# TapDriver-ESP32.net
KiCad netlist of a schematic drawn in Altium Designer
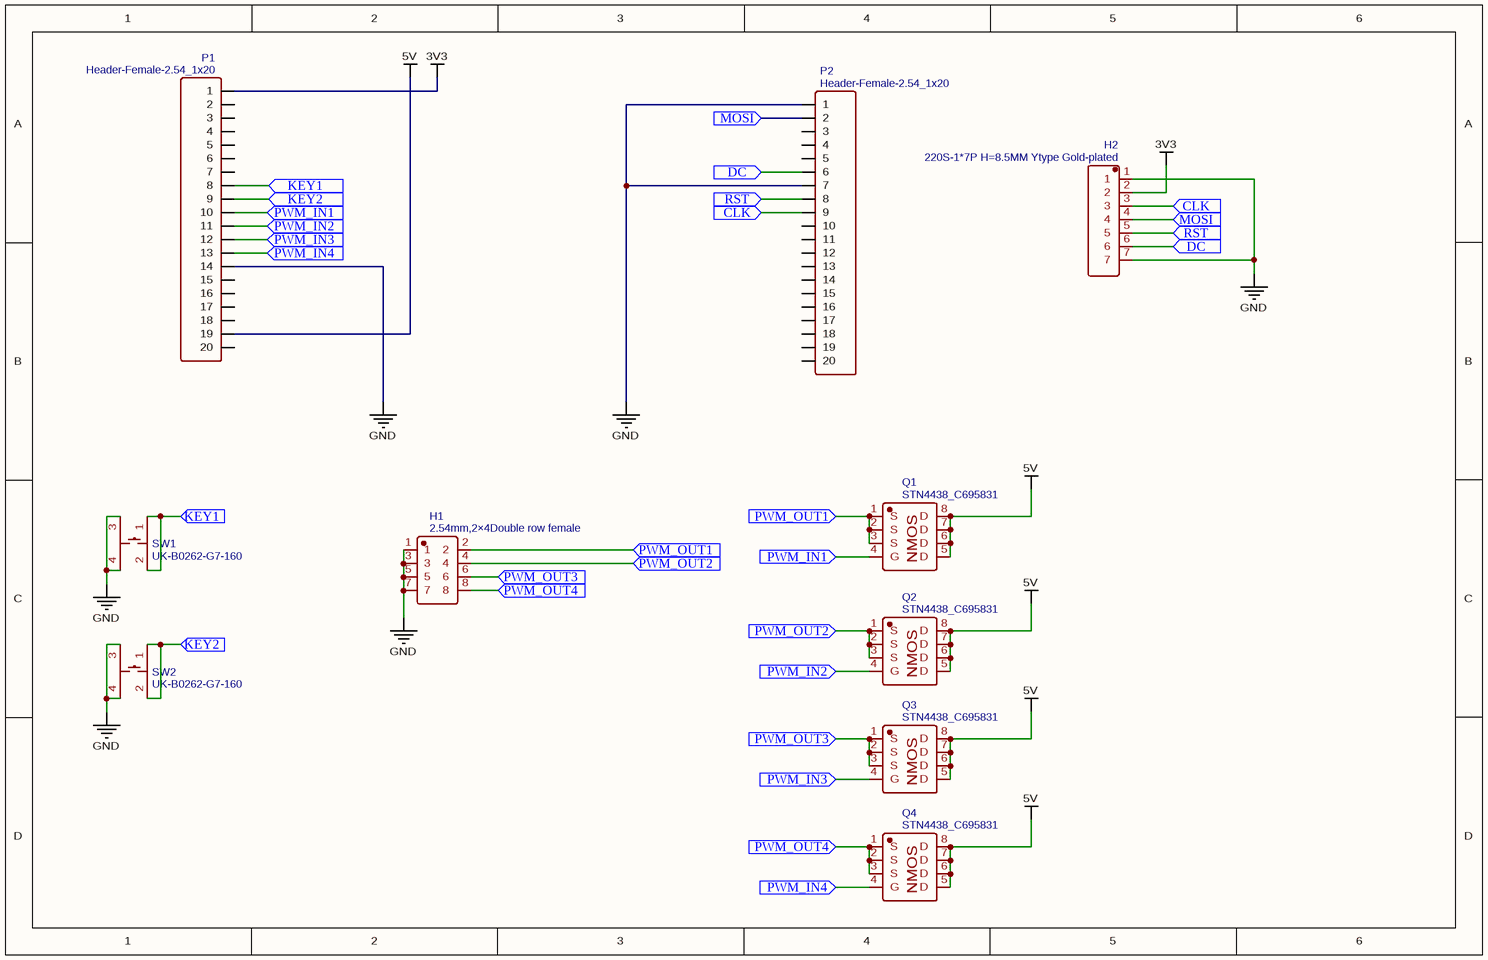
[diagram p0: TapDriver-ESP32.schdoc]

(export (version "E")
  (design (tool "Eeschema 10.0.6"))
  (components
    (comp (ref "H1")
      (value "2.54mm,2×4Double row female")
      (footprint "HDR-TH_8P-P2.54-V-F-R2-C4-S2.54-1")
      (fields (field (name "BOM_SUPPLIER PART") "C58378"))
      (libsource (lib "altium-import") (part "root_0_2.54mm,2×4Double row female_"))
    )
    (comp (ref "H2")
      (value "220S-1*7P H=8.5MM Ytype Gold-plated")
      (footprint "HDR-TH_7P-P2.54-V-F")
      (fields (field (name "BOM_SUPPLIER PART") "C124418") (field (name "CONTRIBUTOR") "LCSC"))
      (libsource (lib "altium-import") (part "root_0_220S-1*7P H=8.5MM Ytype Gold-plated_"))
    )
    (comp (ref "P1")
      (value "Header-Female-2.54_1x20")
      (footprint "HDR-TH_20P-P2.54-V-F")
      (fields
        (field (name "BOM_MANUFACTURER PART") "2.54mm 1*20P Female header")
        (field (name "BOM_SUPPLIER PART") "C50984")
      )
      (libsource (lib "") (part "root_0_Header-Female-2.54_1x20__1"))
    )
    (comp (ref "P2")
      (value "Header-Female-2.54_1x20")
      (footprint "HDR-TH_20P-P2.54-V-F")
      (fields
        (field (name "BOM_MANUFACTURER PART") "2.54mm 1*20P Female header")
        (field (name "BOM_SUPPLIER PART") "C50984")
      )
      (libsource (lib "altium-import") (part "root_0_Header-Female-2.54_1x20_"))
    )
    (comp (ref "Q1")
      (value "STN4438_C695831")
      (footprint "SOP-8_L4.9-W3.9-P1.27-LS6.0-BL")
      (fields
        (field (name "BOM_SUPPLIER PART") "C695831")
        (field (name "BOM_MANUFACTURER PART") "STN4438")
        (field (name "CONTRIBUTOR") "LCSC")
      )
      (libsource (lib "altium-import") (part "root_0_STN4438_C695831_"))
    )
    (comp (ref "Q2")
      (value "STN4438_C695831")
      (footprint "SOP-8_L4.9-W3.9-P1.27-LS6.0-BL")
      (fields
        (field (name "BOM_SUPPLIER PART") "C695831")
        (field (name "BOM_MANUFACTURER PART") "STN4438")
        (field (name "CONTRIBUTOR") "LCSC")
      )
      (libsource (lib "altium-import") (part "root_0_STN4438_C695831_"))
    )
    (comp (ref "Q3")
      (value "STN4438_C695831")
      (footprint "SOP-8_L4.9-W3.9-P1.27-LS6.0-BL")
      (fields
        (field (name "BOM_SUPPLIER PART") "C695831")
        (field (name "BOM_MANUFACTURER PART") "STN4438")
        (field (name "CONTRIBUTOR") "LCSC")
      )
      (libsource (lib "altium-import") (part "root_0_STN4438_C695831_"))
    )
    (comp (ref "Q4")
      (value "STN4438_C695831")
      (footprint "SOP-8_L4.9-W3.9-P1.27-LS6.0-BL")
      (fields
        (field (name "BOM_SUPPLIER PART") "C695831")
        (field (name "BOM_MANUFACTURER PART") "STN4438")
        (field (name "CONTRIBUTOR") "LCSC")
      )
      (libsource (lib "altium-import") (part "root_0_STN4438_C695831_"))
    )
    (comp (ref "SW1")
      (value "UK-B0262-G7-160")
      (footprint "SW-SMD_4P-L12.0-W12.0-P5.00-LS15.0")
      (fields (field (name "BOM_SUPPLIER PART") "C620352") (field (name "CONTRIBUTOR") "LCSC"))
      (libsource (lib "altium-import") (part "root_3_UK-B0262-G7-160_"))
    )
    (comp (ref "SW2")
      (value "UK-B0262-G7-160")
      (footprint "SW-SMD_4P-L12.0-W12.0-P5.00-LS15.0")
      (fields (field (name "BOM_SUPPLIER PART") "C620352") (field (name "CONTRIBUTOR") "LCSC"))
      (libsource (lib "altium-import") (part "root_3_UK-B0262-G7-160_"))
    )
  )
  (nets
    (net (code "1") (name "/CLK") (class "Default")
      (node (ref "H2") (pin "3") (pinfunction "3_3") (pintype "passive"))
      (node (ref "P2") (pin "9") (pinfunction "9_9") (pintype "passive"))
    )
    (net (code "2") (name "/DC") (class "Default")
      (node (ref "H2") (pin "6") (pinfunction "6_6") (pintype "passive"))
      (node (ref "P2") (pin "6") (pinfunction "6_6") (pintype "passive"))
    )
    (net (code "3") (name "/KEY1") (class "Default")
      (node (ref "P1") (pin "8") (pinfunction "8_8") (pintype "passive"))
      (node (ref "SW1") (pin "1") (pinfunction "1_1") (pintype "passive"))
      (node (ref "SW1") (pin "2") (pinfunction "2_2") (pintype "passive"))
    )
    (net (code "4") (name "/KEY2") (class "Default")
      (node (ref "P1") (pin "9") (pinfunction "9_9") (pintype "passive"))
      (node (ref "SW2") (pin "1") (pinfunction "1_1") (pintype "passive"))
      (node (ref "SW2") (pin "2") (pinfunction "2_2") (pintype "passive"))
    )
    (net (code "5") (name "/MOSI") (class "Default")
      (node (ref "H2") (pin "4") (pinfunction "4_4") (pintype "passive"))
      (node (ref "P2") (pin "2") (pinfunction "2_2") (pintype "passive"))
    )
    (net (code "6") (name "/PWM_IN1") (class "Default")
      (node (ref "P1") (pin "10") (pinfunction "10_10") (pintype "passive"))
      (node (ref "Q1") (pin "4") (pinfunction "G_4") (pintype "passive"))
    )
    (net (code "7") (name "/PWM_IN2") (class "Default")
      (node (ref "P1") (pin "11") (pinfunction "11_11") (pintype "passive"))
      (node (ref "Q2") (pin "4") (pinfunction "G_4") (pintype "passive"))
    )
    (net (code "8") (name "/PWM_IN3") (class "Default")
      (node (ref "P1") (pin "12") (pinfunction "12_12") (pintype "passive"))
      (node (ref "Q3") (pin "4") (pinfunction "G_4") (pintype "passive"))
    )
    (net (code "9") (name "/PWM_IN4") (class "Default")
      (node (ref "P1") (pin "13") (pinfunction "13_13") (pintype "passive"))
      (node (ref "Q4") (pin "4") (pinfunction "G_4") (pintype "passive"))
    )
    (net (code "10") (name "/PWM_OUT1") (class "Default")
      (node (ref "H1") (pin "2") (pinfunction "2_2") (pintype "passive"))
      (node (ref "Q1") (pin "1") (pinfunction "S_1") (pintype "passive"))
      (node (ref "Q1") (pin "2") (pinfunction "S_2") (pintype "passive"))
      (node (ref "Q1") (pin "3") (pinfunction "S_3") (pintype "passive"))
    )
    (net (code "11") (name "/PWM_OUT2") (class "Default")
      (node (ref "H1") (pin "4") (pinfunction "4_4") (pintype "passive"))
      (node (ref "Q2") (pin "1") (pinfunction "S_1") (pintype "passive"))
      (node (ref "Q2") (pin "2") (pinfunction "S_2") (pintype "passive"))
      (node (ref "Q2") (pin "3") (pinfunction "S_3") (pintype "passive"))
    )
    (net (code "12") (name "/PWM_OUT3") (class "Default")
      (node (ref "H1") (pin "6") (pinfunction "6_6") (pintype "passive"))
      (node (ref "Q3") (pin "1") (pinfunction "S_1") (pintype "passive"))
      (node (ref "Q3") (pin "2") (pinfunction "S_2") (pintype "passive"))
      (node (ref "Q3") (pin "3") (pinfunction "S_3") (pintype "passive"))
    )
    (net (code "13") (name "/PWM_OUT4") (class "Default")
      (node (ref "H1") (pin "8") (pinfunction "8_8") (pintype "passive"))
      (node (ref "Q4") (pin "1") (pinfunction "S_1") (pintype "passive"))
      (node (ref "Q4") (pin "2") (pinfunction "S_2") (pintype "passive"))
      (node (ref "Q4") (pin "3") (pinfunction "S_3") (pintype "passive"))
    )
    (net (code "14") (name "/RST") (class "Default")
      (node (ref "H2") (pin "5") (pinfunction "5_5") (pintype "passive"))
      (node (ref "P2") (pin "8") (pinfunction "8_8") (pintype "passive"))
    )
    (net (code "15") (name "3V3") (class "Default")
      (node (ref "H2") (pin "2") (pinfunction "2_2") (pintype "passive"))
      (node (ref "P1") (pin "1") (pinfunction "1_1") (pintype "passive"))
    )
    (net (code "16") (name "5V") (class "Default")
      (node (ref "P1") (pin "19") (pinfunction "19_19") (pintype "passive"))
      (node (ref "Q1") (pin "5") (pinfunction "D_5") (pintype "passive"))
      (node (ref "Q1") (pin "6") (pinfunction "D_6") (pintype "passive"))
      (node (ref "Q1") (pin "7") (pinfunction "D_7") (pintype "passive"))
      (node (ref "Q1") (pin "8") (pinfunction "D_8") (pintype "passive"))
      (node (ref "Q2") (pin "5") (pinfunction "D_5") (pintype "passive"))
      (node (ref "Q2") (pin "6") (pinfunction "D_6") (pintype "passive"))
      (node (ref "Q2") (pin "7") (pinfunction "D_7") (pintype "passive"))
      (node (ref "Q2") (pin "8") (pinfunction "D_8") (pintype "passive"))
      (node (ref "Q3") (pin "5") (pinfunction "D_5") (pintype "passive"))
      (node (ref "Q3") (pin "6") (pinfunction "D_6") (pintype "passive"))
      (node (ref "Q3") (pin "7") (pinfunction "D_7") (pintype "passive"))
      (node (ref "Q3") (pin "8") (pinfunction "D_8") (pintype "passive"))
      (node (ref "Q4") (pin "5") (pinfunction "D_5") (pintype "passive"))
      (node (ref "Q4") (pin "6") (pinfunction "D_6") (pintype "passive"))
      (node (ref "Q4") (pin "7") (pinfunction "D_7") (pintype "passive"))
      (node (ref "Q4") (pin "8") (pinfunction "D_8") (pintype "passive"))
    )
    (net (code "17") (name "GND") (class "Default")
      (node (ref "H1") (pin "1") (pinfunction "1_1") (pintype "passive"))
      (node (ref "H1") (pin "3") (pinfunction "3_3") (pintype "passive"))
      (node (ref "H1") (pin "5") (pinfunction "5_5") (pintype "passive"))
      (node (ref "H1") (pin "7") (pinfunction "7_7") (pintype "passive"))
      (node (ref "H2") (pin "1") (pinfunction "1_1") (pintype "passive"))
      (node (ref "H2") (pin "7") (pinfunction "7_7") (pintype "passive"))
      (node (ref "P1") (pin "14") (pinfunction "14_14") (pintype "passive"))
      (node (ref "P2") (pin "1") (pinfunction "1_1") (pintype "passive"))
      (node (ref "P2") (pin "7") (pinfunction "7_7") (pintype "passive"))
      (node (ref "SW1") (pin "3") (pinfunction "3_3") (pintype "passive"))
      (node (ref "SW1") (pin "4") (pinfunction "4_4") (pintype "passive"))
      (node (ref "SW2") (pin "3") (pinfunction "3_3") (pintype "passive"))
      (node (ref "SW2") (pin "4") (pinfunction "4_4") (pintype "passive"))
    )
    (net (code "18") (name "unconnected-(P1-Pad2)") (class "Default")
      (node (ref "P1") (pin "2") (pinfunction "2_2") (pintype "passive"))
    )
    (net (code "19") (name "unconnected-(P1-Pad3)") (class "Default")
      (node (ref "P1") (pin "3") (pinfunction "3_3") (pintype "passive"))
    )
    (net (code "20") (name "unconnected-(P1-Pad4)") (class "Default")
      (node (ref "P1") (pin "4") (pinfunction "4_4") (pintype "passive"))
    )
    (net (code "21") (name "unconnected-(P1-Pad5)") (class "Default")
      (node (ref "P1") (pin "5") (pinfunction "5_5") (pintype "passive"))
    )
    (net (code "22") (name "unconnected-(P1-Pad6)") (class "Default")
      (node (ref "P1") (pin "6") (pinfunction "6_6") (pintype "passive"))
    )
    (net (code "23") (name "unconnected-(P1-Pad7)") (class "Default")
      (node (ref "P1") (pin "7") (pinfunction "7_7") (pintype "passive"))
    )
    (net (code "24") (name "unconnected-(P1-Pad15)") (class "Default")
      (node (ref "P1") (pin "15") (pinfunction "15_15") (pintype "passive"))
    )
    (net (code "25") (name "unconnected-(P1-Pad16)") (class "Default")
      (node (ref "P1") (pin "16") (pinfunction "16_16") (pintype "passive"))
    )
    (net (code "26") (name "unconnected-(P1-Pad17)") (class "Default")
      (node (ref "P1") (pin "17") (pinfunction "17_17") (pintype "passive"))
    )
    (net (code "27") (name "unconnected-(P1-Pad18)") (class "Default")
      (node (ref "P1") (pin "18") (pinfunction "18_18") (pintype "passive"))
    )
    (net (code "28") (name "unconnected-(P1-Pad20)") (class "Default")
      (node (ref "P1") (pin "20") (pinfunction "20_20") (pintype "passive"))
    )
    (net (code "29") (name "unconnected-(P2-Pad3)") (class "Default")
      (node (ref "P2") (pin "3") (pinfunction "3_3") (pintype "passive"))
    )
    (net (code "30") (name "unconnected-(P2-Pad4)") (class "Default")
      (node (ref "P2") (pin "4") (pinfunction "4_4") (pintype "passive"))
    )
    (net (code "31") (name "unconnected-(P2-Pad5)") (class "Default")
      (node (ref "P2") (pin "5") (pinfunction "5_5") (pintype "passive"))
    )
    (net (code "32") (name "unconnected-(P2-Pad10)") (class "Default")
      (node (ref "P2") (pin "10") (pinfunction "10_10") (pintype "passive"))
    )
    (net (code "33") (name "unconnected-(P2-Pad11)") (class "Default")
      (node (ref "P2") (pin "11") (pinfunction "11_11") (pintype "passive"))
    )
    (net (code "34") (name "unconnected-(P2-Pad12)") (class "Default")
      (node (ref "P2") (pin "12") (pinfunction "12_12") (pintype "passive"))
    )
    (net (code "35") (name "unconnected-(P2-Pad13)") (class "Default")
      (node (ref "P2") (pin "13") (pinfunction "13_13") (pintype "passive"))
    )
    (net (code "36") (name "unconnected-(P2-Pad14)") (class "Default")
      (node (ref "P2") (pin "14") (pinfunction "14_14") (pintype "passive"))
    )
    (net (code "37") (name "unconnected-(P2-Pad15)") (class "Default")
      (node (ref "P2") (pin "15") (pinfunction "15_15") (pintype "passive"))
    )
    (net (code "38") (name "unconnected-(P2-Pad16)") (class "Default")
      (node (ref "P2") (pin "16") (pinfunction "16_16") (pintype "passive"))
    )
    (net (code "39") (name "unconnected-(P2-Pad17)") (class "Default")
      (node (ref "P2") (pin "17") (pinfunction "17_17") (pintype "passive"))
    )
    (net (code "40") (name "unconnected-(P2-Pad18)") (class "Default")
      (node (ref "P2") (pin "18") (pinfunction "18_18") (pintype "passive"))
    )
    (net (code "41") (name "unconnected-(P2-Pad19)") (class "Default")
      (node (ref "P2") (pin "19") (pinfunction "19_19") (pintype "passive"))
    )
    (net (code "42") (name "unconnected-(P2-Pad20)") (class "Default")
      (node (ref "P2") (pin "20") (pinfunction "20_20") (pintype "passive"))
    )
  )
)
